# REUN_468349_001_PSU_Board_5B_Interface.net
KiCad netlist of a schematic drawn in Altium Designer
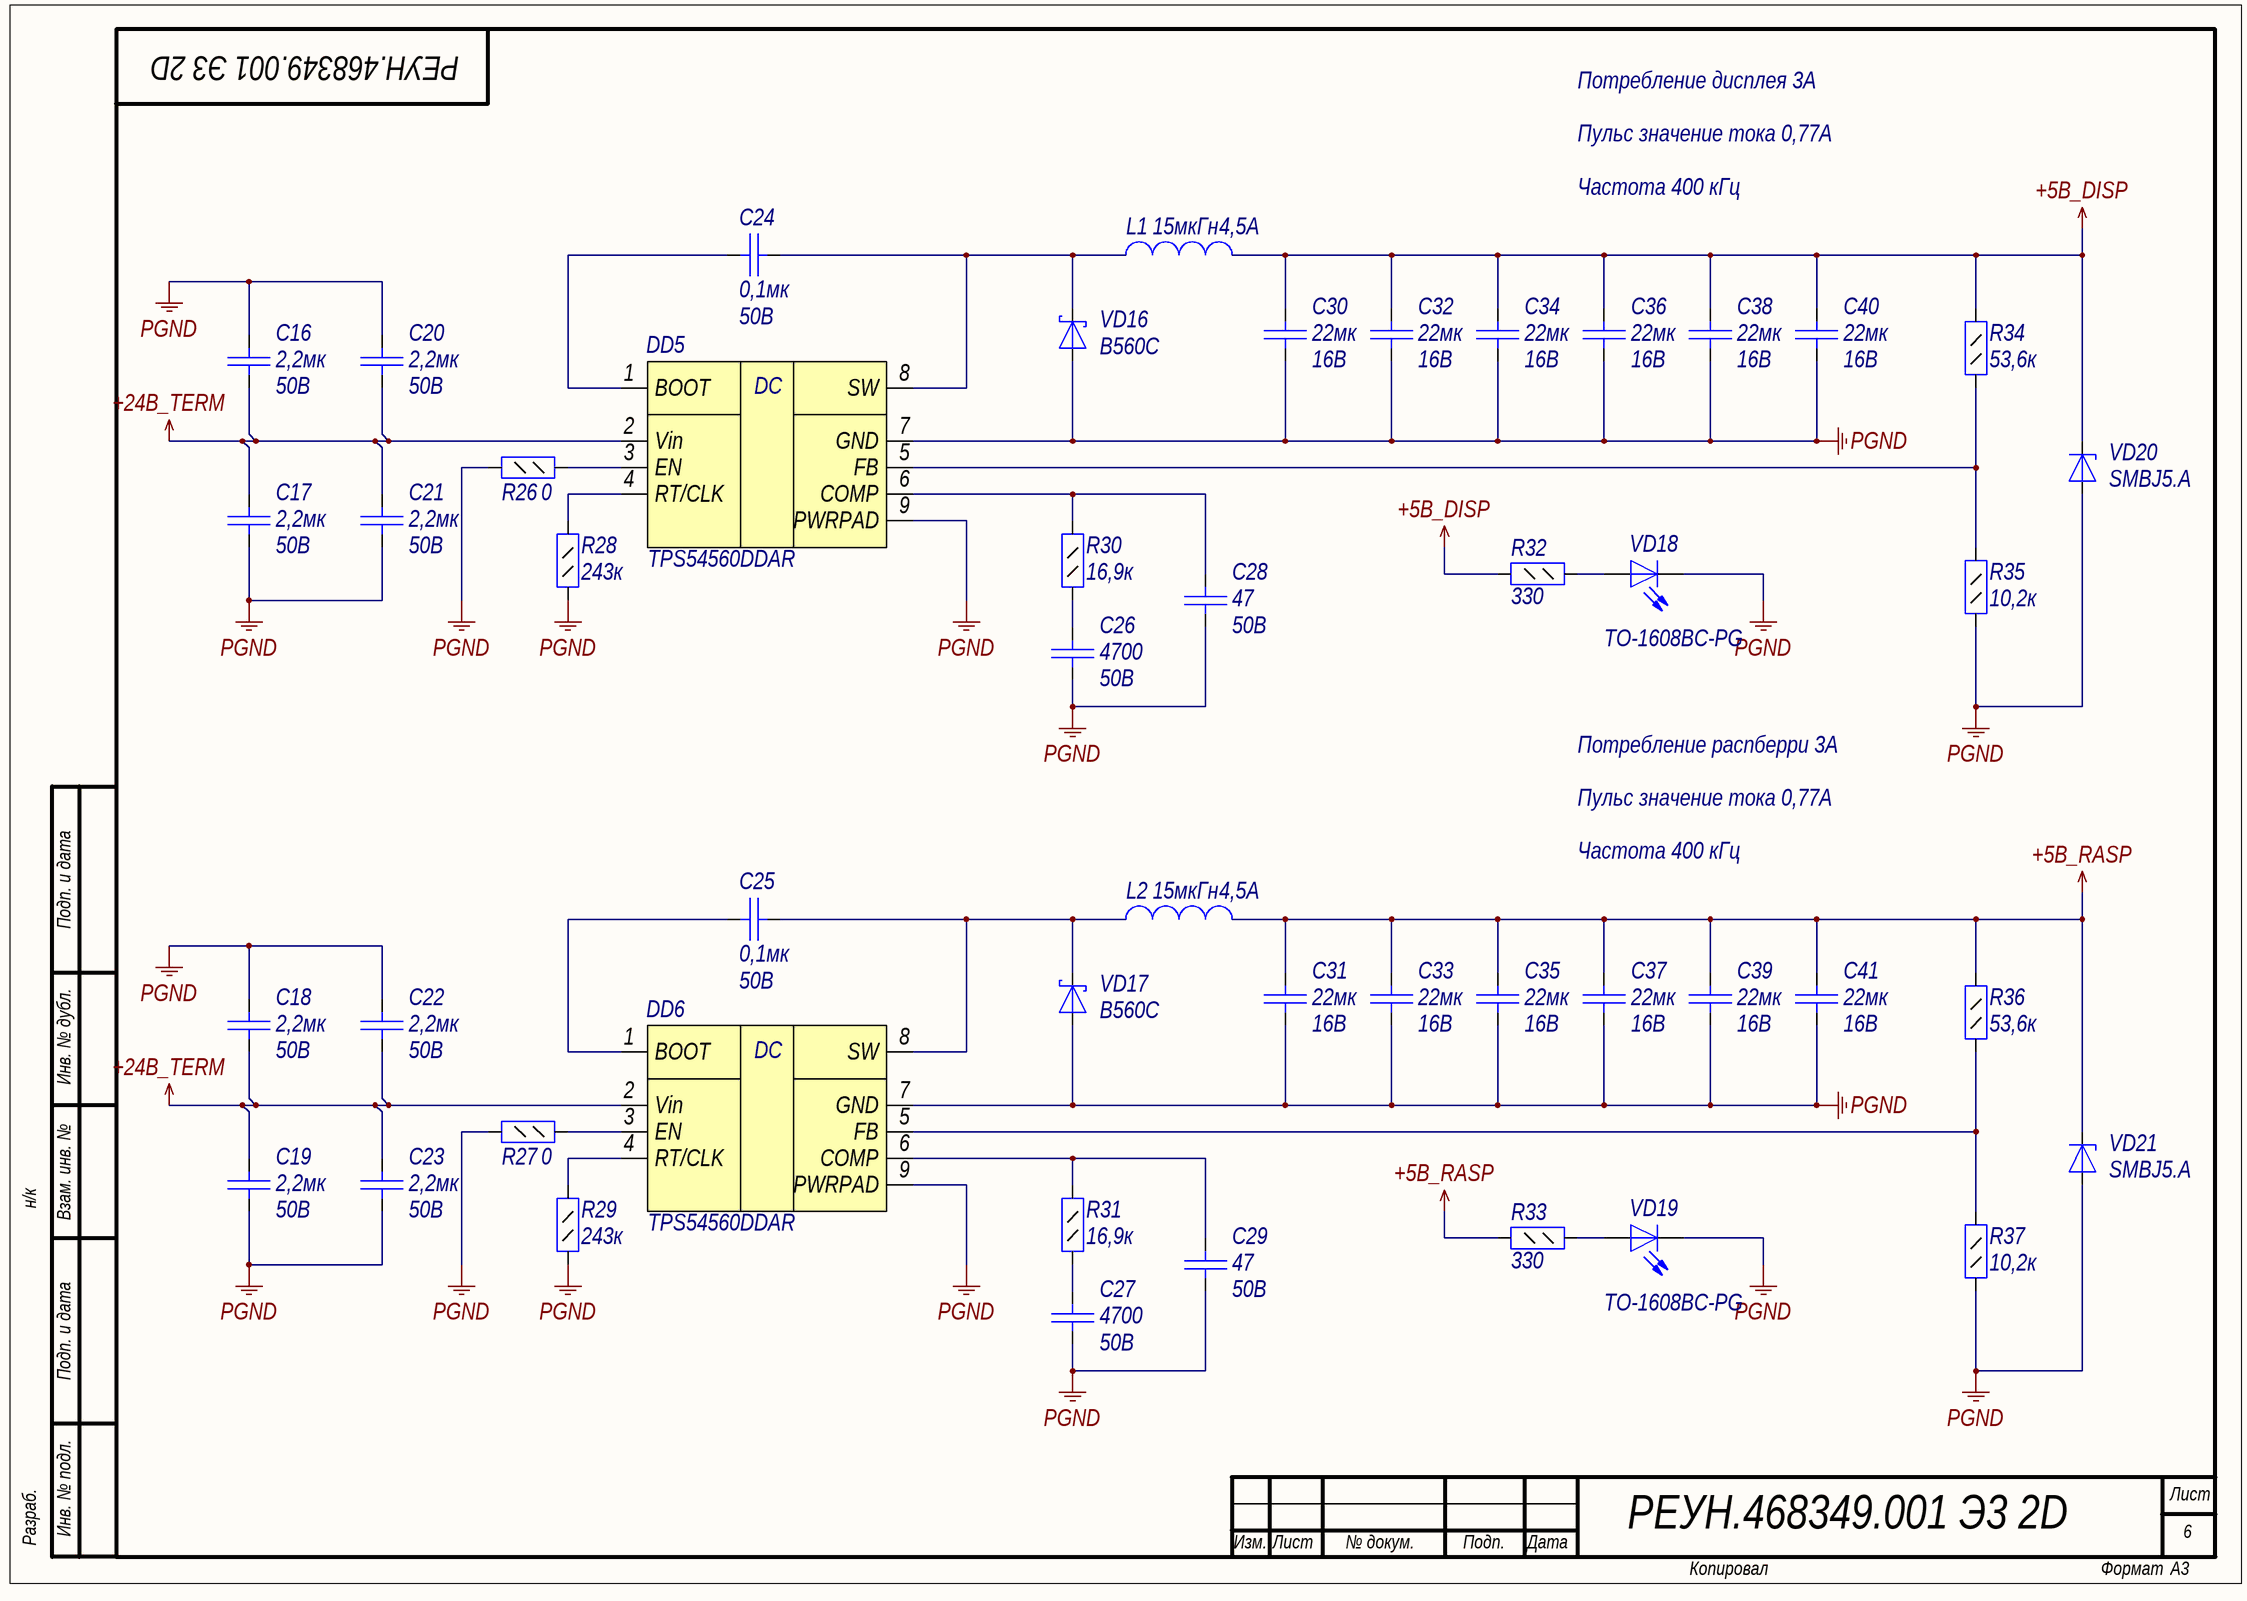
[diagram p0: REUN.468349.001_PSU_Board_5B_Interface.SchDoc]

(export (version "E")
  (design (tool "Eeschema 10.0.6"))
  (components
    (comp (ref "C16")
      (value "2,2мк")
      (footprint "C1206")
      (description "Конденсатор")
      (fields (field (name "VOLTAGE") "50B") (field (name "PART NUMBER") "CL31B225KBHNNNE"))
      (libsource (lib "MOP44") (part "Capacitor"))
    )
    (comp (ref "C17")
      (value "2,2мк")
      (footprint "C1206")
      (description "Конденсатор")
      (fields (field (name "VOLTAGE") "50B") (field (name "PART NUMBER") "CL31B225KBHNNNE"))
      (libsource (lib "MOP44") (part "Capacitor"))
    )
    (comp (ref "C18")
      (value "2,2мк")
      (footprint "C1206")
      (description "Конденсатор")
      (fields (field (name "VOLTAGE") "50B") (field (name "PART NUMBER") "CL31B225KBHNNNE"))
      (libsource (lib "MOP44") (part "Capacitor"))
    )
    (comp (ref "C19")
      (value "2,2мк")
      (footprint "C1206")
      (description "Конденсатор")
      (fields (field (name "VOLTAGE") "50B") (field (name "PART NUMBER") "CL31B225KBHNNNE"))
      (libsource (lib "MOP44") (part "Capacitor"))
    )
    (comp (ref "C20")
      (value "2,2мк")
      (footprint "C1206")
      (description "Конденсатор")
      (fields (field (name "VOLTAGE") "50B") (field (name "PART NUMBER") "CL31B225KBHNNNE"))
      (libsource (lib "MOP44") (part "Capacitor"))
    )
    (comp (ref "C21")
      (value "2,2мк")
      (footprint "C1206")
      (description "Конденсатор")
      (fields (field (name "VOLTAGE") "50B") (field (name "PART NUMBER") "CL31B225KBHNNNE"))
      (libsource (lib "MOP44") (part "Capacitor"))
    )
    (comp (ref "C22")
      (value "2,2мк")
      (footprint "C1206")
      (description "Конденсатор")
      (fields (field (name "VOLTAGE") "50B") (field (name "PART NUMBER") "CL31B225KBHNNNE"))
      (libsource (lib "MOP44") (part "Capacitor"))
    )
    (comp (ref "C23")
      (value "2,2мк")
      (footprint "C1206")
      (description "Конденсатор")
      (fields (field (name "VOLTAGE") "50B") (field (name "PART NUMBER") "CL31B225KBHNNNE"))
      (libsource (lib "MOP44") (part "Capacitor"))
    )
    (comp (ref "C24")
      (value "0,1мк")
      (footprint "C0805")
      (description "Конденсатор")
      (fields (field (name "VOLTAGE") "50B") (field (name "PART NUMBER") "GRM21BR71H104KA01K"))
      (libsource (lib "MOP44") (part "Capacitor"))
    )
    (comp (ref "C25")
      (value "0,1мк")
      (footprint "C0805")
      (description "Конденсатор")
      (fields (field (name "VOLTAGE") "50B") (field (name "PART NUMBER") "GRM21BR71H104KA01K"))
      (libsource (lib "MOP44") (part "Capacitor"))
    )
    (comp (ref "C26")
      (value "4700")
      (footprint "C0805")
      (description "Конденсатор")
      (fields (field (name "VOLTAGE") "50B") (field (name "PART NUMBER") "CC0805KRX7R9BB472"))
      (libsource (lib "MOP44") (part "Capacitor"))
    )
    (comp (ref "C27")
      (value "4700")
      (footprint "C0805")
      (description "Конденсатор")
      (fields (field (name "VOLTAGE") "50B") (field (name "PART NUMBER") "CC0805KRX7R9BB472"))
      (libsource (lib "MOP44") (part "Capacitor"))
    )
    (comp (ref "C28")
      (value "47")
      (footprint "C0805")
      (description "Конденсатор")
      (fields (field (name "VOLTAGE") "50B") (field (name "PART NUMBER") "CC0805JRNPO9BN470"))
      (libsource (lib "MOP44") (part "Capacitor"))
    )
    (comp (ref "C29")
      (value "47")
      (footprint "C0805")
      (description "Конденсатор")
      (fields (field (name "VOLTAGE") "50B") (field (name "PART NUMBER") "CC0805JRNPO9BN470"))
      (libsource (lib "MOP44") (part "Capacitor"))
    )
    (comp (ref "C30")
      (value "22мк")
      (footprint "C1210")
      (description "Конденсатор")
      (fields (field (name "VOLTAGE") "16B") (field (name "PART NUMBER") "CL32B226KOJNNNE"))
      (libsource (lib "MOP44") (part "Capacitor"))
    )
    (comp (ref "C31")
      (value "22мк")
      (footprint "C1210")
      (description "Конденсатор")
      (fields (field (name "VOLTAGE") "16B") (field (name "PART NUMBER") "CL32B226KOJNNNE"))
      (libsource (lib "MOP44") (part "Capacitor"))
    )
    (comp (ref "C32")
      (value "22мк")
      (footprint "C1210")
      (description "Конденсатор")
      (fields (field (name "VOLTAGE") "16B") (field (name "PART NUMBER") "CL32B226KOJNNNE"))
      (libsource (lib "MOP44") (part "Capacitor"))
    )
    (comp (ref "C33")
      (value "22мк")
      (footprint "C1210")
      (description "Конденсатор")
      (fields (field (name "VOLTAGE") "16B") (field (name "PART NUMBER") "CL32B226KOJNNNE"))
      (libsource (lib "MOP44") (part "Capacitor"))
    )
    (comp (ref "C34")
      (value "22мк")
      (footprint "C1210")
      (description "Конденсатор")
      (fields (field (name "VOLTAGE") "16B") (field (name "PART NUMBER") "CL32B226KOJNNNE"))
      (libsource (lib "MOP44") (part "Capacitor"))
    )
    (comp (ref "C35")
      (value "22мк")
      (footprint "C1210")
      (description "Конденсатор")
      (fields (field (name "VOLTAGE") "16B") (field (name "PART NUMBER") "CL32B226KOJNNNE"))
      (libsource (lib "MOP44") (part "Capacitor"))
    )
    (comp (ref "C36")
      (value "22мк")
      (footprint "C1210")
      (description "Конденсатор")
      (fields (field (name "VOLTAGE") "16B") (field (name "PART NUMBER") "CL32B226KOJNNNE"))
      (libsource (lib "MOP44") (part "Capacitor"))
    )
    (comp (ref "C37")
      (value "22мк")
      (footprint "C1210")
      (description "Конденсатор")
      (fields (field (name "VOLTAGE") "16B") (field (name "PART NUMBER") "CL32B226KOJNNNE"))
      (libsource (lib "MOP44") (part "Capacitor"))
    )
    (comp (ref "C38")
      (value "22мк")
      (footprint "C1210")
      (description "Конденсатор")
      (fields (field (name "VOLTAGE") "16B") (field (name "PART NUMBER") "CL32B226KOJNNNE"))
      (libsource (lib "MOP44") (part "Capacitor"))
    )
    (comp (ref "C39")
      (value "22мк")
      (footprint "C1210")
      (description "Конденсатор")
      (fields (field (name "VOLTAGE") "16B") (field (name "PART NUMBER") "CL32B226KOJNNNE"))
      (libsource (lib "MOP44") (part "Capacitor"))
    )
    (comp (ref "C40")
      (value "22мк")
      (footprint "C1210")
      (description "Конденсатор")
      (fields (field (name "VOLTAGE") "16B") (field (name "PART NUMBER") "CL32B226KOJNNNE"))
      (libsource (lib "MOP44") (part "Capacitor"))
    )
    (comp (ref "C41")
      (value "22мк")
      (footprint "C1210")
      (description "Конденсатор")
      (fields (field (name "VOLTAGE") "16B") (field (name "PART NUMBER") "CL32B226KOJNNNE"))
      (libsource (lib "MOP44") (part "Capacitor"))
    )
    (comp (ref "DD5")
      (value "TPS54560DDAR")
      (footprint "SO Powerpad8")
      (description "5-A, Wide Input Range, Step-Down Converter")
      (fields (field (name "MANUFACTURER") "Texas Instruments"))
      (libsource (lib "MOP44") (part "TPS54560"))
    )
    (comp (ref "DD6")
      (value "TPS54560DDAR")
      (footprint "SO Powerpad8")
      (description "5-A, Wide Input Range, Step-Down Converter")
      (fields (field (name "MANUFACTURER") "Texas Instruments"))
      (libsource (lib "MOP44") (part "TPS54560"))
    )
    (comp (ref "L1")
      (value "15мкГн")
      (footprint "IND_12.5x12.5")
      (description "EMI Suppression Filter")
      (fields
        (field (name "RATED CURRENT") "4,5A")
        (field (name "PART NUMBER") "B82477G4153M000")
        (field (name "Comment") "Inductor")
      )
      (libsource (lib "MOP44") (part "Inductor"))
    )
    (comp (ref "L2")
      (value "15мкГн")
      (footprint "IND_12.5x12.5")
      (description "EMI Suppression Filter")
      (fields
        (field (name "RATED CURRENT") "4,5A")
        (field (name "PART NUMBER") "B82477G4153M000")
        (field (name "Comment") "Inductor")
      )
      (libsource (lib "MOP44") (part "Inductor"))
    )
    (comp (ref "R26")
      (value "0")
      (footprint "R0805")
      (description "Резистор")
      (fields (field (name "PART NUMBER") "RC0805FR-070RL") (field (name "POWER") "0,125Вт"))
      (libsource (lib "REUN.468349.001_PSU_Board") (part "res25"))
    )
    (comp (ref "R27")
      (value "0")
      (footprint "R0805")
      (description "Резистор")
      (fields (field (name "PART NUMBER") "RC0805FR-070RL") (field (name "POWER") "0,125Вт"))
      (libsource (lib "REUN.468349.001_PSU_Board") (part "res25"))
    )
    (comp (ref "R28")
      (value "243к")
      (footprint "R0805")
      (description "Резистор")
      (fields (field (name "PART NUMBER") "RC0805FR-07243KL") (field (name "POWER") "0,125Вт"))
      (libsource (lib "MOP44") (part "Resistor_0,125Вт"))
    )
    (comp (ref "R29")
      (value "243к")
      (footprint "R0805")
      (description "Резистор")
      (fields (field (name "PART NUMBER") "RC0805FR-07243KL") (field (name "POWER") "0,125Вт"))
      (libsource (lib "MOP44") (part "Resistor_0,125Вт"))
    )
    (comp (ref "R30")
      (value "16,9к")
      (footprint "R0805")
      (description "Резистор")
      (fields (field (name "PART NUMBER") "RC0805FR-0716K9L") (field (name "POWER") "0,125Вт"))
      (libsource (lib "MOP44") (part "Resistor_0,125Вт"))
    )
    (comp (ref "R31")
      (value "16,9к")
      (footprint "R0805")
      (description "Резистор")
      (fields (field (name "PART NUMBER") "RC0805FR-0716K9L") (field (name "POWER") "0,125Вт"))
      (libsource (lib "MOP44") (part "Resistor_0,125Вт"))
    )
    (comp (ref "R32")
      (value "330")
      (footprint "R0805")
      (description "Резистор")
      (fields (field (name "PART NUMBER") "RC0805FR-07330RL") (field (name "POWER") "0,125Вт"))
      (libsource (lib "") (part "Resistor_0,125Вт_1"))
    )
    (comp (ref "R33")
      (value "330")
      (footprint "R0805")
      (description "Резистор")
      (fields (field (name "PART NUMBER") "RC0805FR-07330RL") (field (name "POWER") "0,125Вт"))
      (libsource (lib "") (part "Resistor_0,125Вт_1"))
    )
    (comp (ref "R34")
      (value "53,6к")
      (footprint "R0805")
      (description "Резистор")
      (fields (field (name "PART NUMBER") "RC0805FR-0753K6L") (field (name "POWER") "0,125Вт"))
      (libsource (lib "MOP44") (part "Resistor_0,125Вт"))
    )
    (comp (ref "R35")
      (value "10,2к")
      (footprint "R0805")
      (description "Резистор")
      (fields (field (name "PART NUMBER") "RC0805FR-0710K2L") (field (name "POWER") "0,125Вт"))
      (libsource (lib "MOP44") (part "Resistor_0,125Вт"))
    )
    (comp (ref "R36")
      (value "53,6к")
      (footprint "R0805")
      (description "Резистор")
      (fields (field (name "PART NUMBER") "RC0805FR-0753K6L") (field (name "POWER") "0,125Вт"))
      (libsource (lib "MOP44") (part "Resistor_0,125Вт"))
    )
    (comp (ref "R37")
      (value "10,2к")
      (footprint "R0805")
      (description "Резистор")
      (fields (field (name "PART NUMBER") "RC0805FR-0710K2L") (field (name "POWER") "0,125Вт"))
      (libsource (lib "MOP44") (part "Resistor_0,125Вт"))
    )
    (comp (ref "VD16")
      (value "B560C")
      (footprint "SMC")
      (description "Диод Шоттки")
      (libsource (lib "MOP44") (part "DiodeSchottky"))
    )
    (comp (ref "VD17")
      (value "B560C")
      (footprint "SMC")
      (description "Диод Шоттки")
      (libsource (lib "MOP44") (part "DiodeSchottky"))
    )
    (comp (ref "VD18")
      (value "TO-1608BC-PG")
      (footprint "L_0603_GREEN")
      (description "Светодиод")
      (libsource (lib "MOP44") (part "LED"))
    )
    (comp (ref "VD19")
      (value "TO-1608BC-PG")
      (footprint "L_0603_GREEN")
      (description "Светодиод")
      (libsource (lib "MOP44") (part "LED"))
    )
    (comp (ref "VD20")
      (value "SMBJ5.A")
      (footprint "SMB")
      (description "Cтабилитрон (лавинный выпрямительный диод) односторонний")
      (libsource (lib "MOP44") (part "DiodeZener"))
    )
    (comp (ref "VD21")
      (value "SMBJ5.A")
      (footprint "SMB")
      (description "Cтабилитрон (лавинный выпрямительный диод) односторонний")
      (libsource (lib "MOP44") (part "DiodeZener"))
    )
  )
  (nets
    (net (code "1") (name "+5B_DISP") (class "Default")
      (node (ref "C30") (pin "2") (pinfunction "2_2") (pintype "passive"))
      (node (ref "C32") (pin "2") (pinfunction "2_2") (pintype "passive"))
      (node (ref "C34") (pin "2") (pinfunction "2_2") (pintype "passive"))
      (node (ref "C36") (pin "2") (pinfunction "2_2") (pintype "passive"))
      (node (ref "C38") (pin "2") (pinfunction "2_2") (pintype "passive"))
      (node (ref "C40") (pin "2") (pinfunction "2_2") (pintype "passive"))
      (node (ref "L1") (pin "2") (pinfunction "2_2") (pintype "passive"))
      (node (ref "R32") (pin "2") (pinfunction "2_2") (pintype "passive"))
      (node (ref "R34") (pin "2") (pinfunction "2_2") (pintype "passive"))
      (node (ref "VD20") (pin "1") (pinfunction "K_1") (pintype "passive"))
    )
    (net (code "2") (name "+5B_RASP") (class "Default")
      (node (ref "C31") (pin "2") (pinfunction "2_2") (pintype "passive"))
      (node (ref "C33") (pin "2") (pinfunction "2_2") (pintype "passive"))
      (node (ref "C35") (pin "2") (pinfunction "2_2") (pintype "passive"))
      (node (ref "C37") (pin "2") (pinfunction "2_2") (pintype "passive"))
      (node (ref "C39") (pin "2") (pinfunction "2_2") (pintype "passive"))
      (node (ref "C41") (pin "2") (pinfunction "2_2") (pintype "passive"))
      (node (ref "L2") (pin "2") (pinfunction "2_2") (pintype "passive"))
      (node (ref "R33") (pin "2") (pinfunction "2_2") (pintype "passive"))
      (node (ref "R36") (pin "2") (pinfunction "2_2") (pintype "passive"))
      (node (ref "VD21") (pin "1") (pinfunction "K_1") (pintype "passive"))
    )
    (net (code "3") (name "+24B_TERM") (class "Default")
      (node (ref "C16") (pin "1") (pinfunction "1_1") (pintype "passive"))
      (node (ref "C17") (pin "2") (pinfunction "2_2") (pintype "passive"))
      (node (ref "C18") (pin "1") (pinfunction "1_1") (pintype "passive"))
      (node (ref "C19") (pin "2") (pinfunction "2_2") (pintype "passive"))
      (node (ref "C20") (pin "1") (pinfunction "1_1") (pintype "passive"))
      (node (ref "C21") (pin "2") (pinfunction "2_2") (pintype "passive"))
      (node (ref "C22") (pin "1") (pinfunction "1_1") (pintype "passive"))
      (node (ref "C23") (pin "2") (pinfunction "2_2") (pintype "passive"))
      (node (ref "DD5") (pin "2") (pinfunction "Vin_2") (pintype "passive"))
      (node (ref "DD6") (pin "2") (pinfunction "Vin_2") (pintype "passive"))
    )
    (net (code "4") (name "Net-(C26-Pad2)") (class "Default")
      (node (ref "C26") (pin "2") (pinfunction "2_2") (pintype "passive"))
      (node (ref "R30") (pin "1") (pinfunction "1_1") (pintype "passive"))
    )
    (net (code "5") (name "Net-(C27-Pad2)") (class "Default")
      (node (ref "C27") (pin "2") (pinfunction "2_2") (pintype "passive"))
      (node (ref "R31") (pin "1") (pinfunction "1_1") (pintype "passive"))
    )
    (net (code "6") (name "Net-(DD5-BOOT)") (class "Default")
      (node (ref "C24") (pin "2") (pinfunction "2_2") (pintype "passive"))
      (node (ref "DD5") (pin "1") (pinfunction "BOOT_1") (pintype "passive"))
    )
    (net (code "7") (name "Net-(DD5-COMP)") (class "Default")
      (node (ref "C28") (pin "2") (pinfunction "2_2") (pintype "passive"))
      (node (ref "DD5") (pin "6") (pinfunction "COMP_6") (pintype "passive"))
      (node (ref "R30") (pin "2") (pinfunction "2_2") (pintype "passive"))
    )
    (net (code "8") (name "Net-(DD5-EN)") (class "Default")
      (node (ref "DD5") (pin "3") (pinfunction "EN_3") (pintype "passive"))
      (node (ref "R26") (pin "1") (pinfunction "1_1") (pintype "passive"))
    )
    (net (code "9") (name "Net-(DD5-FB)") (class "Default")
      (node (ref "DD5") (pin "5") (pinfunction "FB_5") (pintype "passive"))
      (node (ref "R34") (pin "1") (pinfunction "1_1") (pintype "passive"))
      (node (ref "R35") (pin "2") (pinfunction "2_2") (pintype "passive"))
    )
    (net (code "10") (name "Net-(DD5-RT{slash}CLK)") (class "Default")
      (node (ref "DD5") (pin "4") (pinfunction "RT/CLK_4") (pintype "passive"))
      (node (ref "R28") (pin "2") (pinfunction "2_2") (pintype "passive"))
    )
    (net (code "11") (name "Net-(DD5-SW)") (class "Default")
      (node (ref "C24") (pin "1") (pinfunction "1_1") (pintype "passive"))
      (node (ref "DD5") (pin "8") (pinfunction "SW_8") (pintype "passive"))
      (node (ref "L1") (pin "1") (pinfunction "1_1") (pintype "passive"))
      (node (ref "VD16") (pin "1") (pinfunction "K_1") (pintype "passive"))
    )
    (net (code "12") (name "Net-(DD6-BOOT)") (class "Default")
      (node (ref "C25") (pin "2") (pinfunction "2_2") (pintype "passive"))
      (node (ref "DD6") (pin "1") (pinfunction "BOOT_1") (pintype "passive"))
    )
    (net (code "13") (name "Net-(DD6-COMP)") (class "Default")
      (node (ref "C29") (pin "2") (pinfunction "2_2") (pintype "passive"))
      (node (ref "DD6") (pin "6") (pinfunction "COMP_6") (pintype "passive"))
      (node (ref "R31") (pin "2") (pinfunction "2_2") (pintype "passive"))
    )
    (net (code "14") (name "Net-(DD6-EN)") (class "Default")
      (node (ref "DD6") (pin "3") (pinfunction "EN_3") (pintype "passive"))
      (node (ref "R27") (pin "1") (pinfunction "1_1") (pintype "passive"))
    )
    (net (code "15") (name "Net-(DD6-FB)") (class "Default")
      (node (ref "DD6") (pin "5") (pinfunction "FB_5") (pintype "passive"))
      (node (ref "R36") (pin "1") (pinfunction "1_1") (pintype "passive"))
      (node (ref "R37") (pin "2") (pinfunction "2_2") (pintype "passive"))
    )
    (net (code "16") (name "Net-(DD6-RT{slash}CLK)") (class "Default")
      (node (ref "DD6") (pin "4") (pinfunction "RT/CLK_4") (pintype "passive"))
      (node (ref "R29") (pin "2") (pinfunction "2_2") (pintype "passive"))
    )
    (net (code "17") (name "Net-(DD6-SW)") (class "Default")
      (node (ref "C25") (pin "1") (pinfunction "1_1") (pintype "passive"))
      (node (ref "DD6") (pin "8") (pinfunction "SW_8") (pintype "passive"))
      (node (ref "L2") (pin "1") (pinfunction "1_1") (pintype "passive"))
      (node (ref "VD17") (pin "1") (pinfunction "K_1") (pintype "passive"))
    )
    (net (code "18") (name "Net-(VD18-A)") (class "Default")
      (node (ref "R32") (pin "1") (pinfunction "1_1") (pintype "passive"))
      (node (ref "VD18") (pin "2") (pinfunction "A_2") (pintype "passive"))
    )
    (net (code "19") (name "Net-(VD19-A)") (class "Default")
      (node (ref "R33") (pin "1") (pinfunction "1_1") (pintype "passive"))
      (node (ref "VD19") (pin "2") (pinfunction "A_2") (pintype "passive"))
    )
    (net (code "20") (name "PGND") (class "Default")
      (node (ref "C16") (pin "2") (pinfunction "2_2") (pintype "passive"))
      (node (ref "C17") (pin "1") (pinfunction "1_1") (pintype "passive"))
      (node (ref "C18") (pin "2") (pinfunction "2_2") (pintype "passive"))
      (node (ref "C19") (pin "1") (pinfunction "1_1") (pintype "passive"))
      (node (ref "C20") (pin "2") (pinfunction "2_2") (pintype "passive"))
      (node (ref "C21") (pin "1") (pinfunction "1_1") (pintype "passive"))
      (node (ref "C22") (pin "2") (pinfunction "2_2") (pintype "passive"))
      (node (ref "C23") (pin "1") (pinfunction "1_1") (pintype "passive"))
      (node (ref "C26") (pin "1") (pinfunction "1_1") (pintype "passive"))
      (node (ref "C27") (pin "1") (pinfunction "1_1") (pintype "passive"))
      (node (ref "C28") (pin "1") (pinfunction "1_1") (pintype "passive"))
      (node (ref "C29") (pin "1") (pinfunction "1_1") (pintype "passive"))
      (node (ref "C30") (pin "1") (pinfunction "1_1") (pintype "passive"))
      (node (ref "C31") (pin "1") (pinfunction "1_1") (pintype "passive"))
      (node (ref "C32") (pin "1") (pinfunction "1_1") (pintype "passive"))
      (node (ref "C33") (pin "1") (pinfunction "1_1") (pintype "passive"))
      (node (ref "C34") (pin "1") (pinfunction "1_1") (pintype "passive"))
      (node (ref "C35") (pin "1") (pinfunction "1_1") (pintype "passive"))
      (node (ref "C36") (pin "1") (pinfunction "1_1") (pintype "passive"))
      (node (ref "C37") (pin "1") (pinfunction "1_1") (pintype "passive"))
      (node (ref "C38") (pin "1") (pinfunction "1_1") (pintype "passive"))
      (node (ref "C39") (pin "1") (pinfunction "1_1") (pintype "passive"))
      (node (ref "C40") (pin "1") (pinfunction "1_1") (pintype "passive"))
      (node (ref "C41") (pin "1") (pinfunction "1_1") (pintype "passive"))
      (node (ref "DD5") (pin "7") (pinfunction "GND_7") (pintype "passive"))
      (node (ref "DD5") (pin "9") (pinfunction "PWRPAD_9") (pintype "passive"))
      (node (ref "DD6") (pin "7") (pinfunction "GND_7") (pintype "passive"))
      (node (ref "DD6") (pin "9") (pinfunction "PWRPAD_9") (pintype "passive"))
      (node (ref "R26") (pin "2") (pinfunction "2_2") (pintype "passive"))
      (node (ref "R27") (pin "2") (pinfunction "2_2") (pintype "passive"))
      (node (ref "R28") (pin "1") (pinfunction "1_1") (pintype "passive"))
      (node (ref "R29") (pin "1") (pinfunction "1_1") (pintype "passive"))
      (node (ref "R35") (pin "1") (pinfunction "1_1") (pintype "passive"))
      (node (ref "R37") (pin "1") (pinfunction "1_1") (pintype "passive"))
      (node (ref "VD16") (pin "2") (pinfunction "A_2") (pintype "passive"))
      (node (ref "VD17") (pin "2") (pinfunction "A_2") (pintype "passive"))
      (node (ref "VD18") (pin "1") (pinfunction "K_1") (pintype "passive"))
      (node (ref "VD19") (pin "1") (pinfunction "K_1") (pintype "passive"))
      (node (ref "VD20") (pin "2") (pinfunction "A_2") (pintype "passive"))
      (node (ref "VD21") (pin "2") (pinfunction "A_2") (pintype "passive"))
    )
  )
)
